# softstart.net
KiCad netlist of a schematic drawn in EAGLE
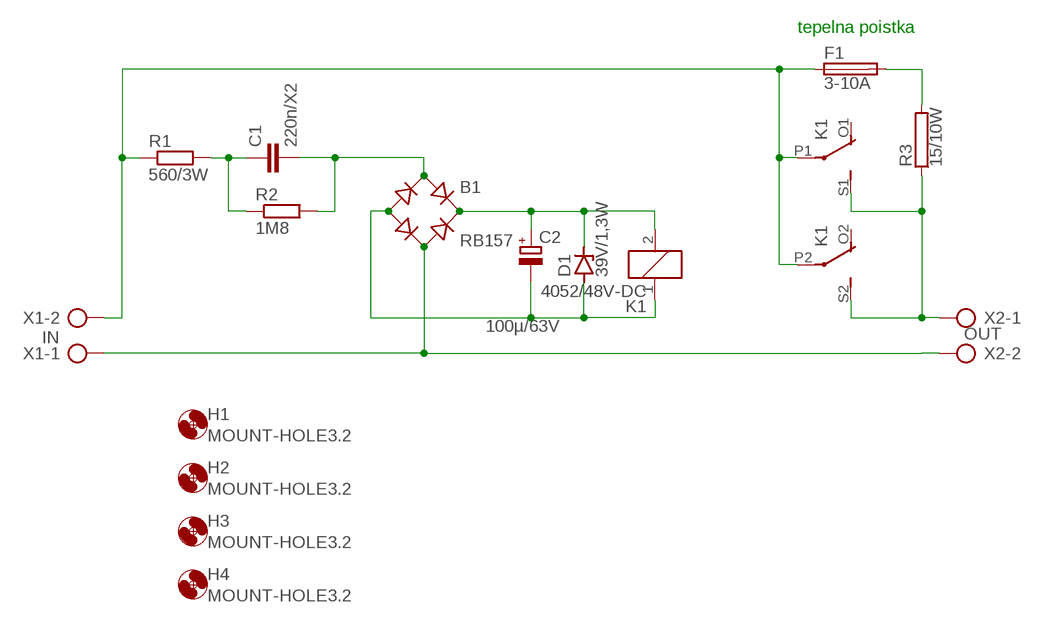
[diagram p0: schematic, sheet 1]

(export (version "E")
  (design (tool "Eeschema 10.0.6"))
  (components
    (comp (ref "B1")
      (value "RB157")
      (footprint "eagle-import:RB1A")
      (libsource (lib "eagle-import") (part "RB1A"))
    )
    (comp (ref "C1")
      (value "220n/X2")
      (footprint "eagle-import:C150-072X183")
      (libsource (lib "eagle-import") (part "C-EU150-072X183"))
    )
    (comp (ref "C2")
      (value "100µ/63V")
      (footprint "eagle-import:E5-10,5")
      (libsource (lib "eagle-import") (part "CPOL-EUE5-10.5"))
    )
    (comp (ref "D1")
      (value "39V/1,3W")
      (footprint "eagle-import:DO35Z10")
      (libsource (lib "eagle-import") (part "ZENER-DIODEDO35Z10"))
    )
    (comp (ref "F1")
      (value "3-10A")
      (footprint "eagle-import:TE5")
      (libsource (lib "eagle-import") (part "TE5"))
    )
    (comp (ref "H1")
      (value "MOUNT-HOLE3.2")
      (footprint "eagle-import:3,2")
      (libsource (lib "eagle-import") (part "MOUNT-HOLE3.2"))
    )
    (comp (ref "H2")
      (value "MOUNT-HOLE3.2")
      (footprint "eagle-import:3,2")
      (libsource (lib "eagle-import") (part "MOUNT-HOLE3.2"))
    )
    (comp (ref "H3")
      (value "MOUNT-HOLE3.2")
      (footprint "eagle-import:3,2")
      (libsource (lib "eagle-import") (part "MOUNT-HOLE3.2"))
    )
    (comp (ref "H4")
      (value "MOUNT-HOLE3.2")
      (footprint "eagle-import:3,2")
      (libsource (lib "eagle-import") (part "MOUNT-HOLE3.2"))
    )
    (comp (ref "K1")
      (value "4052/48V-DC")
      (footprint "eagle-import:F4052")
      (libsource (lib "eagle-import") (part "4052"))
    )
    (comp (ref "R1")
      (value "560/3W")
      (footprint "eagle-import:0617_22")
      (libsource (lib "eagle-import") (part "R-EU_0617/22"))
    )
    (comp (ref "R2")
      (value "1M8")
      (footprint "eagle-import:0207_10")
      (libsource (lib "eagle-import") (part "R-EU_0207/10"))
    )
    (comp (ref "R3")
      (value "15/10W")
      (footprint "eagle-import:RWM10X49")
      (libsource (lib "eagle-import") (part "RRWM10X49"))
    )
    (comp (ref "X1")
      (value "IN")
      (footprint "eagle-import:AK500_2")
      (libsource (lib "eagle-import") (part "AK500/2"))
    )
    (comp (ref "X2")
      (value "OUT")
      (footprint "eagle-import:AK500_2")
      (libsource (lib "eagle-import") (part "AK500/2"))
    )
  )
  (nets
    (net (code "1") (name "Net-(B1-Pad+)") (class "Default")
      (node (ref "B1") (pin "+") (pinfunction "+_+") (pintype "passive"))
      (node (ref "C2") (pin "+") (pinfunction "+_+") (pintype "passive"))
      (node (ref "D1") (pin "C") (pinfunction "C_C") (pintype "passive"))
      (node (ref "K1") (pin "2") (pinfunction "2_2") (pintype "passive"))
    )
    (net (code "2") (name "Net-(B1-Pad-)") (class "Default")
      (node (ref "B1") (pin "-") (pinfunction "-_-") (pintype "passive"))
      (node (ref "C2") (pin "-") (pinfunction "-_-") (pintype "passive"))
      (node (ref "D1") (pin "A") (pinfunction "A_A") (pintype "passive"))
      (node (ref "K1") (pin "1") (pinfunction "1_1") (pintype "passive"))
    )
    (net (code "3") (name "Net-(B1-PadAC1)") (class "Default")
      (node (ref "B1") (pin "AC1") (pinfunction "AC1_AC1") (pintype "passive"))
      (node (ref "C1") (pin "2") (pinfunction "2_2") (pintype "passive"))
      (node (ref "R2") (pin "2") (pinfunction "2_2") (pintype "passive"))
    )
    (net (code "4") (name "Net-(C1-Pad1)") (class "Default")
      (node (ref "C1") (pin "1") (pinfunction "1_1") (pintype "passive"))
      (node (ref "R1") (pin "2") (pinfunction "2_2") (pintype "passive"))
      (node (ref "R2") (pin "1") (pinfunction "1_1") (pintype "passive"))
    )
    (net (code "5") (name "Net-(F1-Pad2)") (class "Default")
      (node (ref "F1") (pin "2") (pinfunction "2_2") (pintype "passive"))
      (node (ref "R3") (pin "2") (pinfunction "2_2") (pintype "passive"))
    )
    (net (code "6") (name "Net-(K1B-P)") (class "Default")
      (node (ref "F1") (pin "1") (pinfunction "1_1") (pintype "passive"))
      (node (ref "K1") (pin "P1") (pinfunction "P_P1") (pintype "passive"))
      (node (ref "K1") (pin "P2") (pinfunction "P_P2") (pintype "passive"))
      (node (ref "R1") (pin "1") (pinfunction "1_1") (pintype "passive"))
      (node (ref "X1") (pin "2") (pinfunction "KL_2") (pintype "passive"))
    )
    (net (code "7") (name "Net-(K1B-S)") (class "Default")
      (node (ref "K1") (pin "S1") (pinfunction "S_S1") (pintype "passive"))
      (node (ref "K1") (pin "S2") (pinfunction "S_S2") (pintype "passive"))
      (node (ref "R3") (pin "1") (pinfunction "1_1") (pintype "passive"))
      (node (ref "X2") (pin "1") (pinfunction "KL_1") (pintype "passive"))
    )
    (net (code "8") (name "Net-(X1A-KL)") (class "Default")
      (node (ref "B1") (pin "AC2") (pinfunction "AC2_AC2") (pintype "passive"))
      (node (ref "X1") (pin "1") (pinfunction "KL_1") (pintype "passive"))
      (node (ref "X2") (pin "2") (pinfunction "KL_2") (pintype "passive"))
    )
    (net (code "9") (name "unconnected-(K1B-O-PadO1)") (class "Default")
      (node (ref "K1") (pin "O1") (pinfunction "O_O1") (pintype "passive"))
    )
    (net (code "10") (name "unconnected-(K1C-O-PadO2)") (class "Default")
      (node (ref "K1") (pin "O2") (pinfunction "O_O2") (pintype "passive"))
    )
  )
)
